# IMU_final.net
KiCad netlist of a schematic drawn in EAGLE
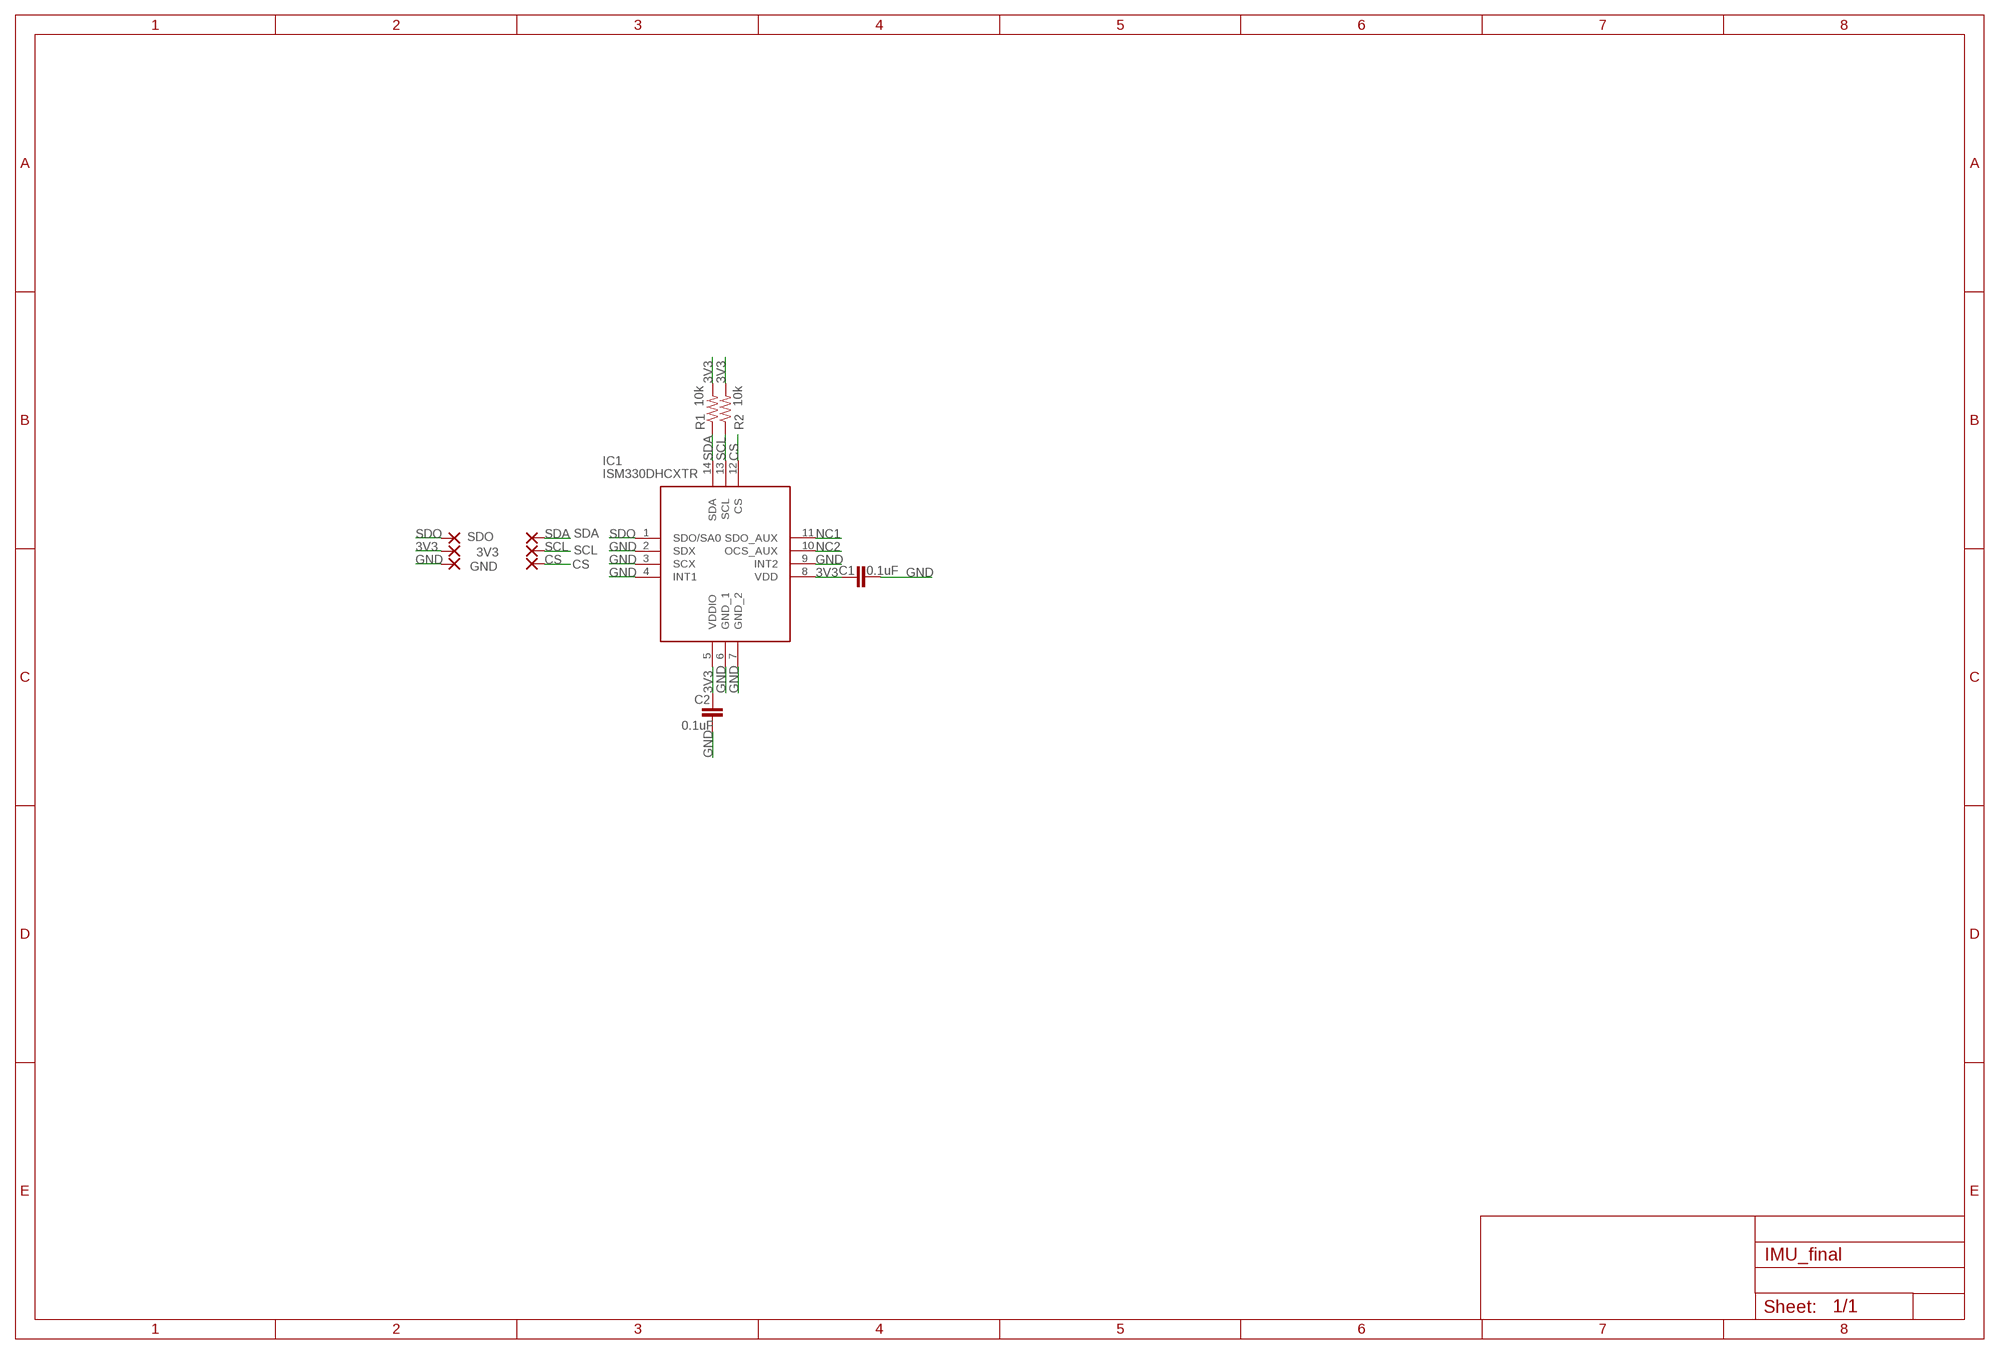
[diagram p0: schematic, sheet 1]

(export (version "E")
  (design (tool "Eeschema 10.0.6"))
  (components
    (comp (ref "3V3")
      (value "SMD5")
      (footprint "eagle-import:SMD2,54-5,08")
      (libsource (lib "eagle-import") (part "SMD5"))
    )
    (comp (ref "C1")
      (value "0.1uF")
      (footprint "eagle-import:0603")
      (libsource (lib "eagle-import") (part "0.1UF-0603-25V-(+80/-20%)"))
    )
    (comp (ref "C2")
      (value "0.1uF")
      (footprint "eagle-import:0603")
      (libsource (lib "eagle-import") (part "0.1UF-0603-25V-(+80/-20%)"))
    )
    (comp (ref "CS")
      (value "SMD5")
      (footprint "eagle-import:SMD2,54-5,08")
      (libsource (lib "eagle-import") (part "SMD5"))
    )
    (comp (ref "GND")
      (value "SMD5")
      (footprint "eagle-import:SMD2,54-5,08")
      (libsource (lib "eagle-import") (part "SMD5"))
    )
    (comp (ref "IC1")
      (value "ISM330DHCXTR")
      (footprint "eagle-import:LGA-14(2.5X3X0.86)")
      (fields (field (name "MOUSER_PART_NUMBER") "511-ISM330DHCXTR"))
      (libsource (lib "eagle-import") (part "ISM330DHCXTR"))
    )
    (comp (ref "R1")
      (value "10k")
      (footprint "eagle-import:0603")
      (libsource (lib "eagle-import") (part "10KOHM-0603-1/10W-1%"))
    )
    (comp (ref "R2")
      (value "10k")
      (footprint "eagle-import:0603")
      (libsource (lib "eagle-import") (part "10KOHM-0603-1/10W-1%"))
    )
    (comp (ref "SCL")
      (value "SMD5")
      (footprint "eagle-import:SMD2,54-5,08")
      (libsource (lib "eagle-import") (part "SMD5"))
    )
    (comp (ref "SDA")
      (value "SMD5")
      (footprint "eagle-import:SMD2,54-5,08")
      (libsource (lib "eagle-import") (part "SMD5"))
    )
    (comp (ref "SDO")
      (value "SMD5")
      (footprint "eagle-import:SMD2,54-5,08")
      (libsource (lib "eagle-import") (part "SMD5"))
    )
  )
  (nets
    (net (code "1") (name "/3V3") (class "Default")
      (node (ref "3V3") (pin "1") (pinfunction "P_1") (pintype "passive"))
      (node (ref "C1") (pin "1") (pinfunction "1_1") (pintype "passive"))
      (node (ref "C2") (pin "1") (pinfunction "1_1") (pintype "passive"))
      (node (ref "IC1") (pin "5") (pinfunction "VDDIO_5") (pintype "bidirectional"))
      (node (ref "IC1") (pin "8") (pinfunction "VDD_8") (pintype "bidirectional"))
      (node (ref "R1") (pin "2") (pinfunction "2_2") (pintype "passive"))
      (node (ref "R2") (pin "2") (pinfunction "2_2") (pintype "passive"))
    )
    (net (code "2") (name "/CS") (class "Default")
      (node (ref "CS") (pin "1") (pinfunction "P_1") (pintype "passive"))
      (node (ref "IC1") (pin "12") (pinfunction "CS_12") (pintype "bidirectional"))
    )
    (net (code "3") (name "/GND") (class "Default")
      (node (ref "C1") (pin "2") (pinfunction "2_2") (pintype "passive"))
      (node (ref "C2") (pin "2") (pinfunction "2_2") (pintype "passive"))
      (node (ref "GND") (pin "1") (pinfunction "P_1") (pintype "passive"))
      (node (ref "IC1") (pin "2") (pinfunction "SDX_2") (pintype "bidirectional"))
      (node (ref "IC1") (pin "3") (pinfunction "SCX_3") (pintype "bidirectional"))
      (node (ref "IC1") (pin "4") (pinfunction "INT1_4") (pintype "bidirectional"))
      (node (ref "IC1") (pin "6") (pinfunction "GND_1_6") (pintype "bidirectional"))
      (node (ref "IC1") (pin "7") (pinfunction "GND_2_7") (pintype "bidirectional"))
      (node (ref "IC1") (pin "9") (pinfunction "INT2_9") (pintype "bidirectional"))
    )
    (net (code "4") (name "/NC1") (class "Default")
      (node (ref "IC1") (pin "11") (pinfunction "SDO_AUX_11") (pintype "bidirectional"))
    )
    (net (code "5") (name "/NC2") (class "Default")
      (node (ref "IC1") (pin "10") (pinfunction "OCS_AUX_10") (pintype "bidirectional"))
    )
    (net (code "6") (name "/SCL") (class "Default")
      (node (ref "IC1") (pin "13") (pinfunction "SCL_13") (pintype "bidirectional"))
      (node (ref "R2") (pin "1") (pinfunction "1_1") (pintype "passive"))
      (node (ref "SCL") (pin "1") (pinfunction "P_1") (pintype "passive"))
    )
    (net (code "7") (name "/SDA") (class "Default")
      (node (ref "IC1") (pin "14") (pinfunction "SDA_14") (pintype "bidirectional"))
      (node (ref "R1") (pin "1") (pinfunction "1_1") (pintype "passive"))
      (node (ref "SDA") (pin "1") (pinfunction "P_1") (pintype "passive"))
    )
    (net (code "8") (name "/SDO") (class "Default")
      (node (ref "IC1") (pin "1") (pinfunction "SDO/SA0_1") (pintype "bidirectional"))
      (node (ref "SDO") (pin "1") (pinfunction "P_1") (pintype "passive"))
    )
  )
)
